# TopBoardLidar.net
KiCad netlist of a schematic drawn in EAGLE
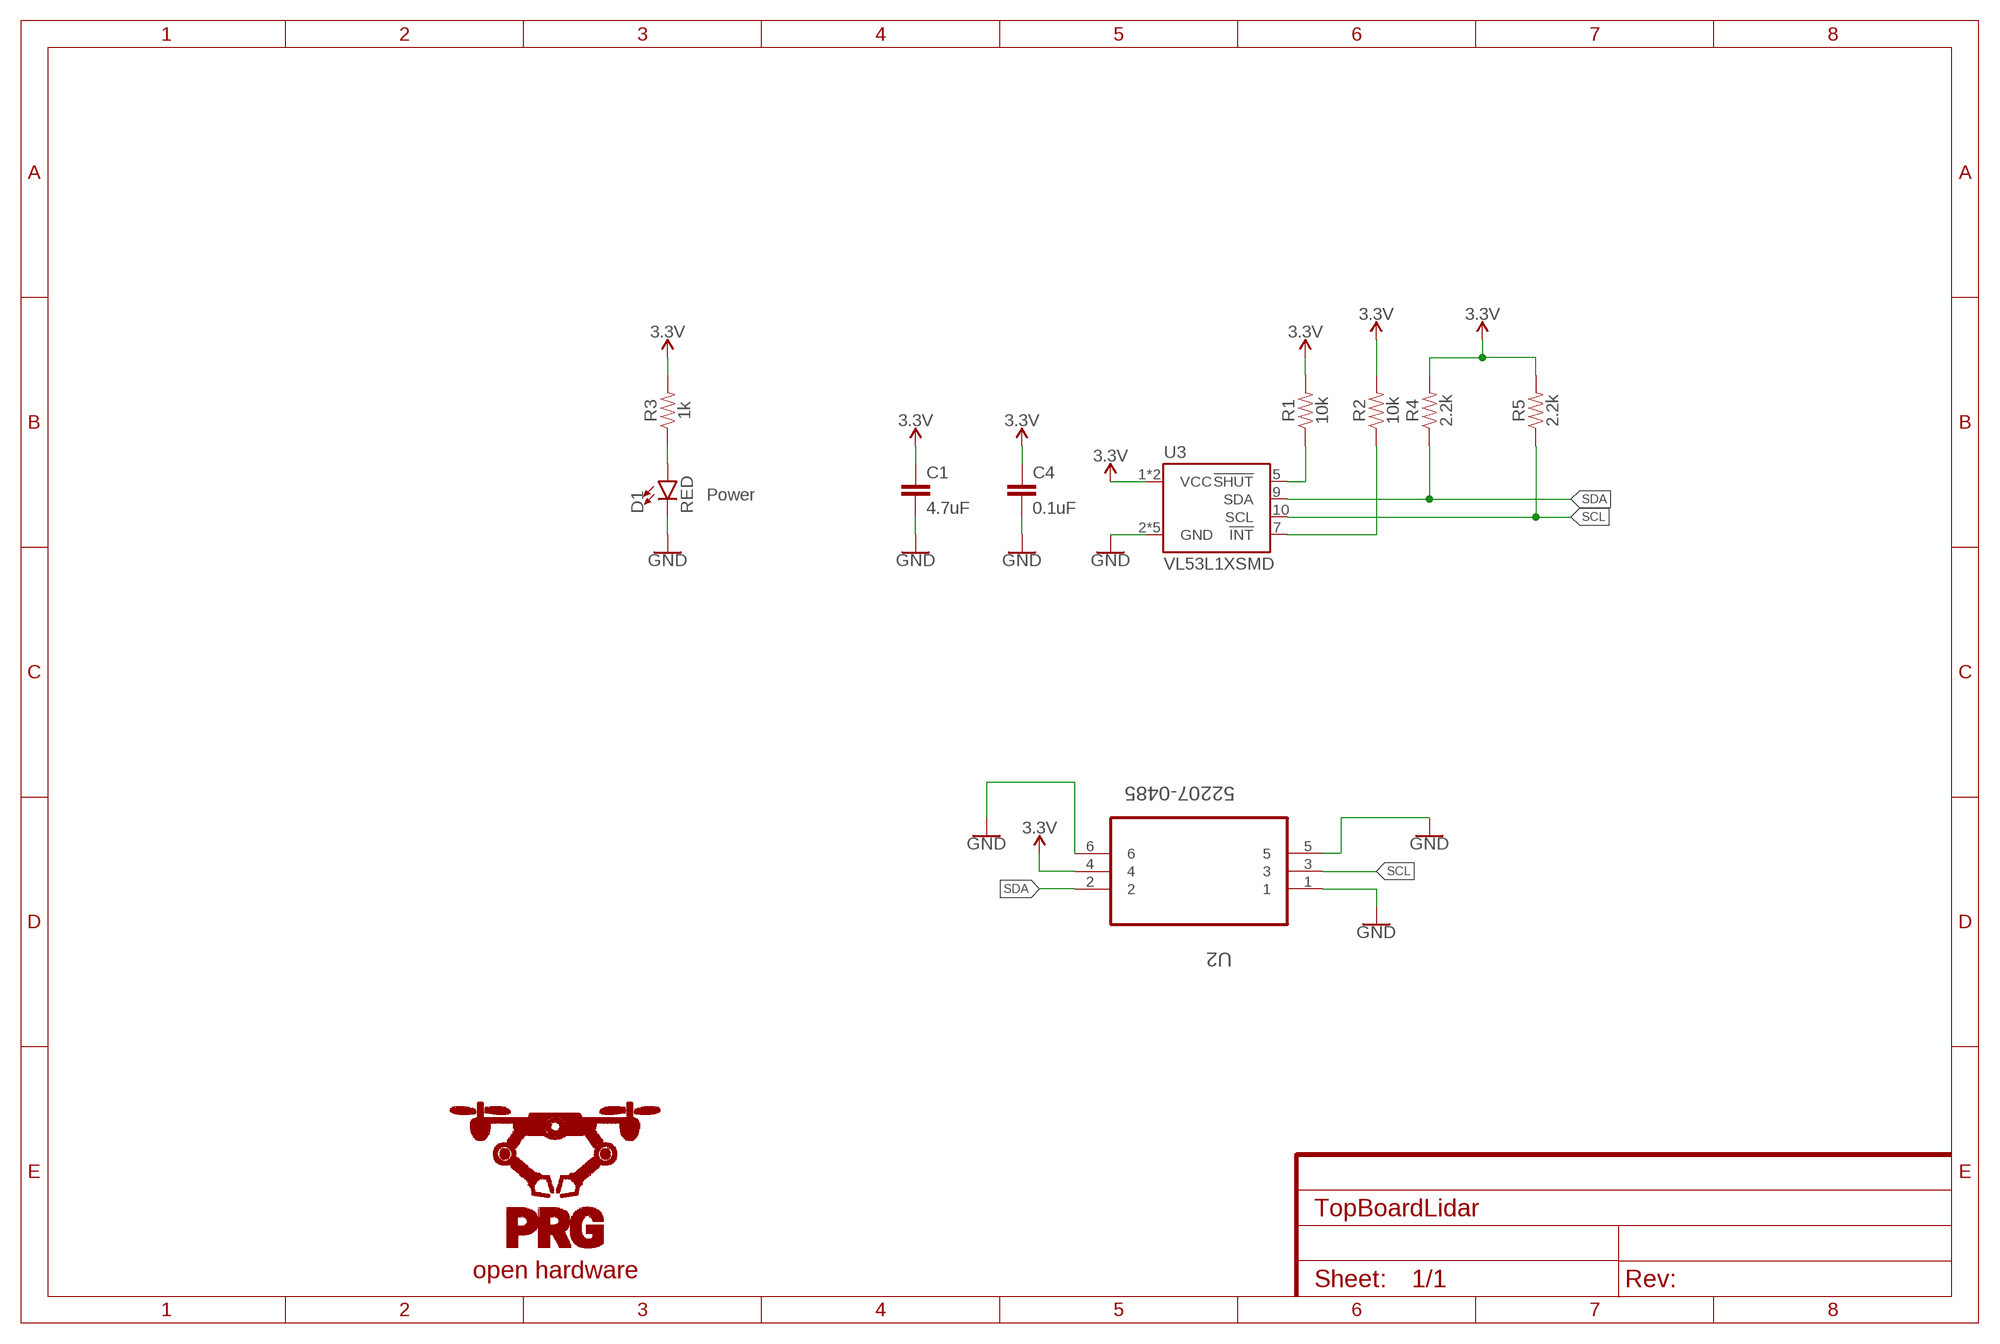
[diagram p0: schematic, sheet 1]

(export (version "E")
  (design (tool "Eeschema 10.0.6"))
  (components
    (comp (ref "C1")
      (value "4.7uF")
      (footprint "eagle-import:0603")
      (libsource (lib "eagle-import") (part "4.7UF0603"))
    )
    (comp (ref "C4")
      (value "0.1uF")
      (footprint "eagle-import:0603")
      (libsource (lib "eagle-import") (part "0.1UF-0603-25V-(+80/-20%)"))
    )
    (comp (ref "D1")
      (value "RED")
      (footprint "eagle-import:LED-0603")
      (libsource (lib "eagle-import") (part "LED-RED0603"))
    )
    (comp (ref "R1")
      (value "10k")
      (footprint "eagle-import:0603")
      (libsource (lib "eagle-import") (part "10KOHM-0603-1/10W-1%"))
    )
    (comp (ref "R2")
      (value "10k")
      (footprint "eagle-import:0603")
      (libsource (lib "eagle-import") (part "10KOHM-0603-1/10W-1%"))
    )
    (comp (ref "R3")
      (value "1k")
      (footprint "eagle-import:0603")
      (libsource (lib "eagle-import") (part "1KOHM-0603-1/10W-1%"))
    )
    (comp (ref "R4")
      (value "2.2k")
      (footprint "eagle-import:0402-TIGHT")
      (libsource (lib "eagle-import") (part "2.2KOHM-0402T-1/16W-1%"))
    )
    (comp (ref "R5")
      (value "2.2k")
      (footprint "eagle-import:0402-TIGHT")
      (libsource (lib "eagle-import") (part "2.2KOHM-0402T-1/16W-1%"))
    )
    (comp (ref "U2")
      (value "52207-0485")
      (footprint "eagle-import:MOLEX_52207-0485")
      (libsource (lib "eagle-import") (part "52207-0485"))
    )
    (comp (ref "U3")
      (value "VL53L1XSMD")
      (footprint "eagle-import:VL53L1X")
      (libsource (lib "eagle-import") (part "VL53L1XSMD"))
    )
  )
  (nets
    (net (code "1") (name "3.3V") (class "Default")
      (node (ref "C1") (pin "1") (pinfunction "1_1") (pintype "passive"))
      (node (ref "C4") (pin "1") (pinfunction "1_1") (pintype "passive"))
      (node (ref "R1") (pin "2") (pinfunction "2_2") (pintype "passive"))
      (node (ref "R2") (pin "2") (pinfunction "2_2") (pintype "passive"))
      (node (ref "R3") (pin "2") (pinfunction "2_2") (pintype "passive"))
      (node (ref "R4") (pin "2") (pinfunction "2_2") (pintype "passive"))
      (node (ref "R5") (pin "2") (pinfunction "2_2") (pintype "passive"))
      (node (ref "U2") (pin "4") (pinfunction "4_4") (pintype "passive"))
      (node (ref "U3") (pin "1") (pinfunction "VCC_1") (pintype "bidirectional"))
      (node (ref "U3") (pin "11") (pinfunction "VCC_11") (pintype "bidirectional"))
    )
    (net (code "2") (name "GND") (class "Default")
      (node (ref "C1") (pin "2") (pinfunction "2_2") (pintype "passive"))
      (node (ref "C4") (pin "2") (pinfunction "2_2") (pintype "passive"))
      (node (ref "D1") (pin "C") (pinfunction "C_C") (pintype "passive"))
      (node (ref "U2") (pin "1") (pinfunction "1_1") (pintype "passive"))
      (node (ref "U2") (pin "5") (pinfunction "5_5") (pintype "passive"))
      (node (ref "U2") (pin "6") (pinfunction "6_6") (pintype "passive"))
      (node (ref "U3") (pin "12") (pinfunction "GND_12") (pintype "bidirectional"))
      (node (ref "U3") (pin "2") (pinfunction "GND_2") (pintype "bidirectional"))
      (node (ref "U3") (pin "3") (pinfunction "GND_3") (pintype "bidirectional"))
      (node (ref "U3") (pin "4") (pinfunction "GND_4") (pintype "bidirectional"))
      (node (ref "U3") (pin "6") (pinfunction "GND_6") (pintype "bidirectional"))
    )
    (net (code "3") (name "Net-(D1-PadA)") (class "Default")
      (node (ref "D1") (pin "A") (pinfunction "A_A") (pintype "passive"))
      (node (ref "R3") (pin "1") (pinfunction "1_1") (pintype "passive"))
    )
    (net (code "4") (name "Net-(U3-~{INT})") (class "Default")
      (node (ref "R2") (pin "1") (pinfunction "1_1") (pintype "passive"))
      (node (ref "U3") (pin "7") (pinfunction "~{INT}_7") (pintype "bidirectional"))
    )
    (net (code "5") (name "Net-(U3-~{SHUT})") (class "Default")
      (node (ref "R1") (pin "1") (pinfunction "1_1") (pintype "passive"))
      (node (ref "U3") (pin "5") (pinfunction "~{SHUT}_5") (pintype "bidirectional"))
    )
    (net (code "6") (name "SCL") (class "Default")
      (node (ref "R5") (pin "1") (pinfunction "1_1") (pintype "passive"))
      (node (ref "U2") (pin "3") (pinfunction "3_3") (pintype "passive"))
      (node (ref "U3") (pin "10") (pinfunction "SCL_10") (pintype "bidirectional"))
    )
    (net (code "7") (name "SDA") (class "Default")
      (node (ref "R4") (pin "1") (pinfunction "1_1") (pintype "passive"))
      (node (ref "U2") (pin "2") (pinfunction "2_2") (pintype "passive"))
      (node (ref "U3") (pin "9") (pinfunction "SDA_9") (pintype "bidirectional"))
    )
  )
)
